# schemat.net
KiCad netlist of a schematic drawn in EAGLE
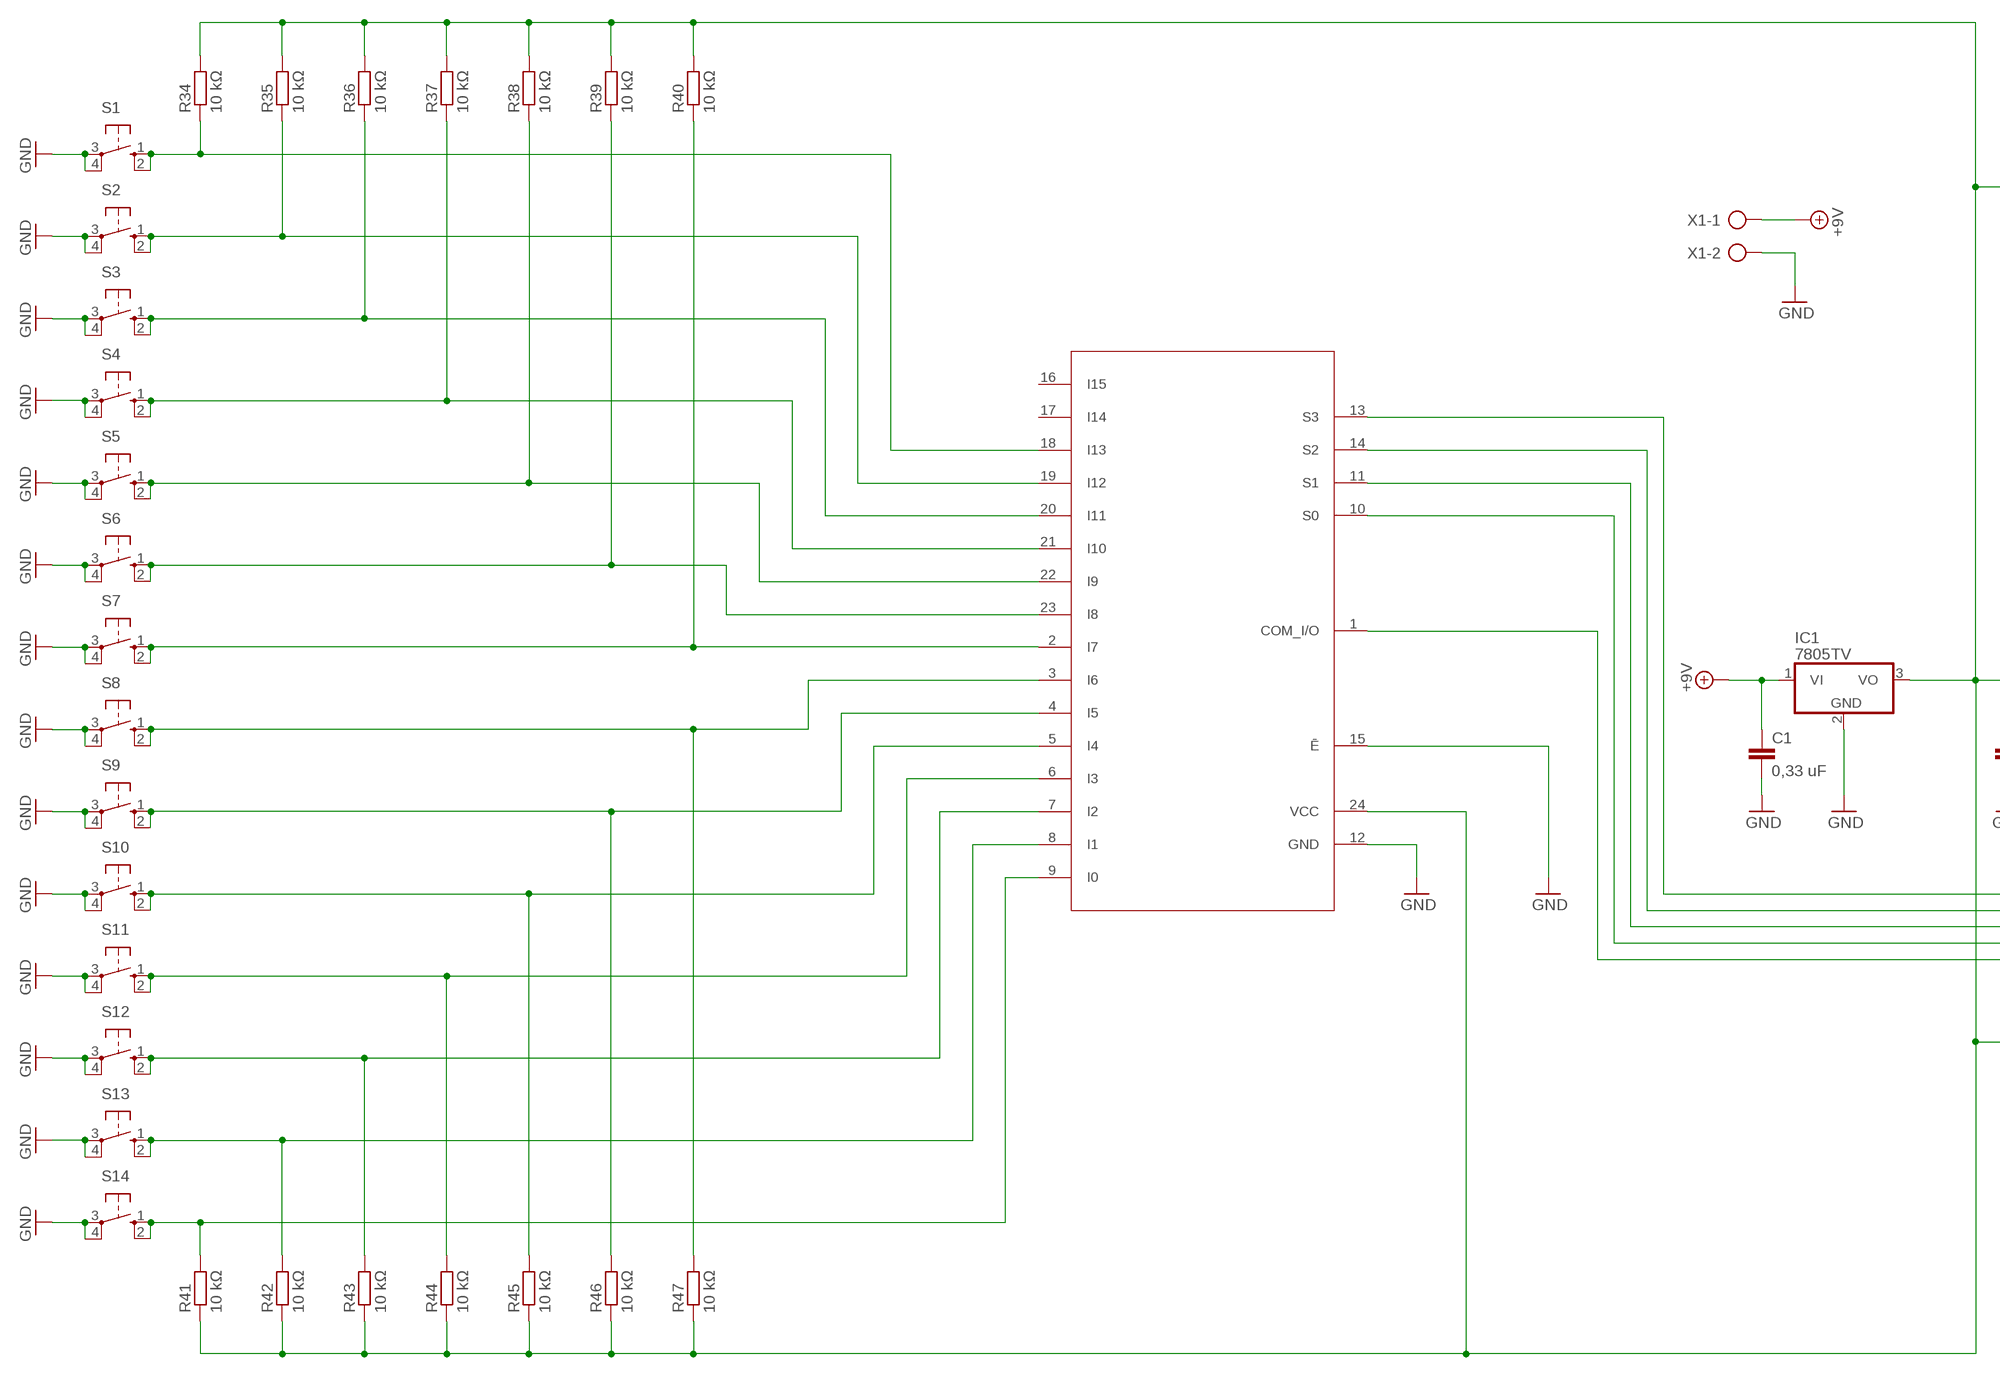
[diagram p0: schematic, sheet 1, part 1 of 2]
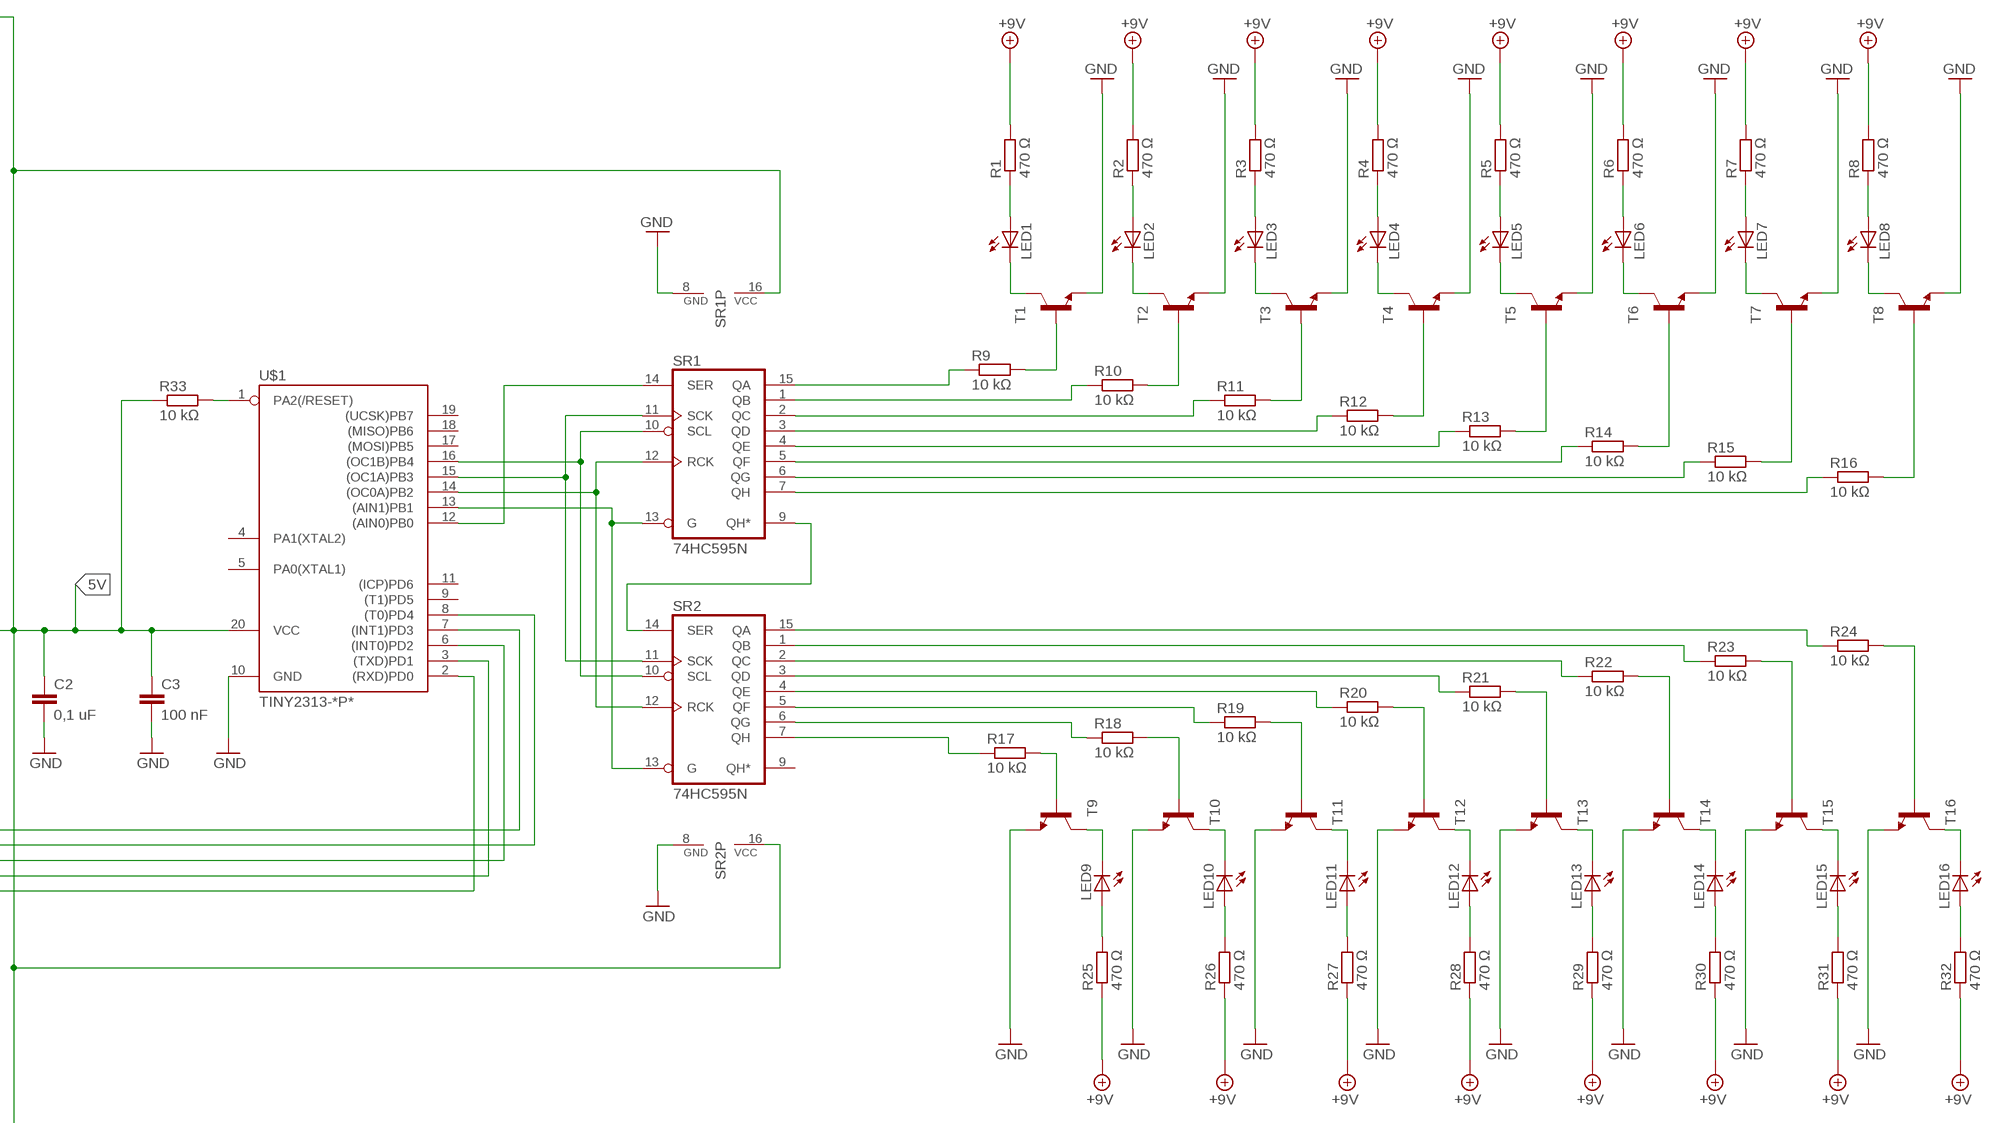
[diagram p1: schematic, sheet 1, part 2 of 2]

(export (version "E")
  (design (tool "Eeschema 10.0.6"))
  (components
    (comp (ref "C1")
      (value "0,33 uF")
      (footprint "eagle-import:C025-024X044")
      (libsource (lib "eagle-import") (part "C-EU025-024X044"))
    )
    (comp (ref "C2")
      (value "0,1 uF")
      (footprint "eagle-import:C025-024X044")
      (libsource (lib "eagle-import") (part "C-EU025-024X044"))
    )
    (comp (ref "C3")
      (value "100 nF")
      (footprint "eagle-import:C025-024X044")
      (libsource (lib "eagle-import") (part "C-EU025-024X044"))
    )
    (comp (ref "IC1")
      (value "7805TV")
      (footprint "eagle-import:TO220V")
      (libsource (lib "eagle-import") (part "78TV05"))
    )
    (comp (ref "LED1")
      (value "LED5MM")
      (footprint "eagle-import:LED5MM")
      (libsource (lib "eagle-import") (part "LED5MM"))
    )
    (comp (ref "LED2")
      (value "LED5MM")
      (footprint "eagle-import:LED5MM")
      (libsource (lib "eagle-import") (part "LED5MM"))
    )
    (comp (ref "LED3")
      (value "LED5MM")
      (footprint "eagle-import:LED5MM")
      (libsource (lib "eagle-import") (part "LED5MM"))
    )
    (comp (ref "LED4")
      (value "LED5MM")
      (footprint "eagle-import:LED5MM")
      (libsource (lib "eagle-import") (part "LED5MM"))
    )
    (comp (ref "LED5")
      (value "LED5MM")
      (footprint "eagle-import:LED5MM")
      (libsource (lib "eagle-import") (part "LED5MM"))
    )
    (comp (ref "LED6")
      (value "LED5MM")
      (footprint "eagle-import:LED5MM")
      (libsource (lib "eagle-import") (part "LED5MM"))
    )
    (comp (ref "LED7")
      (value "LED5MM")
      (footprint "eagle-import:LED5MM")
      (libsource (lib "eagle-import") (part "LED5MM"))
    )
    (comp (ref "LED8")
      (value "LED5MM")
      (footprint "eagle-import:LED5MM")
      (libsource (lib "eagle-import") (part "LED5MM"))
    )
    (comp (ref "LED9")
      (value "LED5MM")
      (footprint "eagle-import:LED5MM")
      (libsource (lib "eagle-import") (part "LED5MM"))
    )
    (comp (ref "LED10")
      (value "LED5MM")
      (footprint "eagle-import:LED5MM")
      (libsource (lib "eagle-import") (part "LED5MM"))
    )
    (comp (ref "LED11")
      (value "LED5MM")
      (footprint "eagle-import:LED5MM")
      (libsource (lib "eagle-import") (part "LED5MM"))
    )
    (comp (ref "LED12")
      (value "LED5MM")
      (footprint "eagle-import:LED5MM")
      (libsource (lib "eagle-import") (part "LED5MM"))
    )
    (comp (ref "LED13")
      (value "LED5MM")
      (footprint "eagle-import:LED5MM")
      (libsource (lib "eagle-import") (part "LED5MM"))
    )
    (comp (ref "LED14")
      (value "LED5MM")
      (footprint "eagle-import:LED5MM")
      (libsource (lib "eagle-import") (part "LED5MM"))
    )
    (comp (ref "LED15")
      (value "LED5MM")
      (footprint "eagle-import:LED5MM")
      (libsource (lib "eagle-import") (part "LED5MM"))
    )
    (comp (ref "LED16")
      (value "LED5MM")
      (footprint "eagle-import:LED5MM")
      (libsource (lib "eagle-import") (part "LED5MM"))
    )
    (comp (ref "R1")
      (value "470 Ω")
      (footprint "eagle-import:0207_10")
      (libsource (lib "eagle-import") (part "R-EU_0207/10"))
    )
    (comp (ref "R2")
      (value "470 Ω")
      (footprint "eagle-import:0207_10")
      (libsource (lib "eagle-import") (part "R-EU_0207/10"))
    )
    (comp (ref "R3")
      (value "470 Ω")
      (footprint "eagle-import:0207_10")
      (libsource (lib "eagle-import") (part "R-EU_0207/10"))
    )
    (comp (ref "R4")
      (value "470 Ω")
      (footprint "eagle-import:0207_10")
      (libsource (lib "eagle-import") (part "R-EU_0207/10"))
    )
    (comp (ref "R5")
      (value "470 Ω")
      (footprint "eagle-import:0207_10")
      (libsource (lib "eagle-import") (part "R-EU_0207/10"))
    )
    (comp (ref "R6")
      (value "470 Ω")
      (footprint "eagle-import:0207_10")
      (libsource (lib "eagle-import") (part "R-EU_0207/10"))
    )
    (comp (ref "R7")
      (value "470 Ω")
      (footprint "eagle-import:0207_10")
      (libsource (lib "eagle-import") (part "R-EU_0207/10"))
    )
    (comp (ref "R8")
      (value "470 Ω")
      (footprint "eagle-import:0207_10")
      (libsource (lib "eagle-import") (part "R-EU_0207/10"))
    )
    (comp (ref "R9")
      (value "10 kΩ")
      (footprint "eagle-import:0207_10")
      (libsource (lib "eagle-import") (part "R-EU_0207/10"))
    )
    (comp (ref "R10")
      (value "10 kΩ")
      (footprint "eagle-import:0207_10")
      (libsource (lib "eagle-import") (part "R-EU_0207/10"))
    )
    (comp (ref "R11")
      (value "10 kΩ")
      (footprint "eagle-import:0207_10")
      (libsource (lib "eagle-import") (part "R-EU_0207/10"))
    )
    (comp (ref "R12")
      (value "10 kΩ")
      (footprint "eagle-import:0207_10")
      (libsource (lib "eagle-import") (part "R-EU_0207/10"))
    )
    (comp (ref "R13")
      (value "10 kΩ")
      (footprint "eagle-import:0207_10")
      (libsource (lib "eagle-import") (part "R-EU_0207/10"))
    )
    (comp (ref "R14")
      (value "10 kΩ")
      (footprint "eagle-import:0207_10")
      (libsource (lib "eagle-import") (part "R-EU_0207/10"))
    )
    (comp (ref "R15")
      (value "10 kΩ")
      (footprint "eagle-import:0207_10")
      (libsource (lib "eagle-import") (part "R-EU_0207/10"))
    )
    (comp (ref "R16")
      (value "10 kΩ")
      (footprint "eagle-import:0207_10")
      (libsource (lib "eagle-import") (part "R-EU_0207/10"))
    )
    (comp (ref "R17")
      (value "10 kΩ")
      (footprint "eagle-import:0207_10")
      (libsource (lib "eagle-import") (part "R-EU_0207/10"))
    )
    (comp (ref "R18")
      (value "10 kΩ")
      (footprint "eagle-import:0207_10")
      (libsource (lib "eagle-import") (part "R-EU_0207/10"))
    )
    (comp (ref "R19")
      (value "10 kΩ")
      (footprint "eagle-import:0207_10")
      (libsource (lib "eagle-import") (part "R-EU_0207/10"))
    )
    (comp (ref "R20")
      (value "10 kΩ")
      (footprint "eagle-import:0207_10")
      (libsource (lib "eagle-import") (part "R-EU_0207/10"))
    )
    (comp (ref "R21")
      (value "10 kΩ")
      (footprint "eagle-import:0207_10")
      (libsource (lib "eagle-import") (part "R-EU_0207/10"))
    )
    (comp (ref "R22")
      (value "10 kΩ")
      (footprint "eagle-import:0207_10")
      (libsource (lib "eagle-import") (part "R-EU_0207/10"))
    )
    (comp (ref "R23")
      (value "10 kΩ")
      (footprint "eagle-import:0207_10")
      (libsource (lib "eagle-import") (part "R-EU_0207/10"))
    )
    (comp (ref "R24")
      (value "10 kΩ")
      (footprint "eagle-import:0207_10")
      (libsource (lib "eagle-import") (part "R-EU_0207/10"))
    )
    (comp (ref "R25")
      (value "470 Ω")
      (footprint "eagle-import:0207_10")
      (libsource (lib "eagle-import") (part "R-EU_0207/10"))
    )
    (comp (ref "R26")
      (value "470 Ω")
      (footprint "eagle-import:0207_10")
      (libsource (lib "eagle-import") (part "R-EU_0207/10"))
    )
    (comp (ref "R27")
      (value "470 Ω")
      (footprint "eagle-import:0207_10")
      (libsource (lib "eagle-import") (part "R-EU_0207/10"))
    )
    (comp (ref "R28")
      (value "470 Ω")
      (footprint "eagle-import:0207_10")
      (libsource (lib "eagle-import") (part "R-EU_0207/10"))
    )
    (comp (ref "R29")
      (value "470 Ω")
      (footprint "eagle-import:0207_10")
      (libsource (lib "eagle-import") (part "R-EU_0207/10"))
    )
    (comp (ref "R30")
      (value "470 Ω")
      (footprint "eagle-import:0207_10")
      (libsource (lib "eagle-import") (part "R-EU_0207/10"))
    )
    (comp (ref "R31")
      (value "470 Ω")
      (footprint "eagle-import:0207_10")
      (libsource (lib "eagle-import") (part "R-EU_0207/10"))
    )
    (comp (ref "R32")
      (value "470 Ω")
      (footprint "eagle-import:0207_10")
      (libsource (lib "eagle-import") (part "R-EU_0207/10"))
    )
    (comp (ref "R33")
      (value "10 kΩ")
      (footprint "eagle-import:0207_10")
      (libsource (lib "eagle-import") (part "R-EU_0207/10"))
    )
    (comp (ref "R34")
      (value "10 kΩ")
      (footprint "eagle-import:0207_10")
      (libsource (lib "eagle-import") (part "R-EU_0207/10"))
    )
    (comp (ref "R35")
      (value "10 kΩ")
      (footprint "eagle-import:0207_10")
      (libsource (lib "eagle-import") (part "R-EU_0207/10"))
    )
    (comp (ref "R36")
      (value "10 kΩ")
      (footprint "eagle-import:0207_10")
      (libsource (lib "eagle-import") (part "R-EU_0207/10"))
    )
    (comp (ref "R37")
      (value "10 kΩ")
      (footprint "eagle-import:0207_10")
      (libsource (lib "eagle-import") (part "R-EU_0207/10"))
    )
    (comp (ref "R38")
      (value "10 kΩ")
      (footprint "eagle-import:0207_10")
      (libsource (lib "eagle-import") (part "R-EU_0207/10"))
    )
    (comp (ref "R39")
      (value "10 kΩ")
      (footprint "eagle-import:0207_10")
      (libsource (lib "eagle-import") (part "R-EU_0207/10"))
    )
    (comp (ref "R40")
      (value "10 kΩ")
      (footprint "eagle-import:0207_10")
      (libsource (lib "eagle-import") (part "R-EU_0207/10"))
    )
    (comp (ref "R41")
      (value "10 kΩ")
      (footprint "eagle-import:0207_10")
      (libsource (lib "eagle-import") (part "R-EU_0207/10"))
    )
    (comp (ref "R42")
      (value "10 kΩ")
      (footprint "eagle-import:0207_10")
      (libsource (lib "eagle-import") (part "R-EU_0207/10"))
    )
    (comp (ref "R43")
      (value "10 kΩ")
      (footprint "eagle-import:0207_10")
      (libsource (lib "eagle-import") (part "R-EU_0207/10"))
    )
    (comp (ref "R44")
      (value "10 kΩ")
      (footprint "eagle-import:0207_10")
      (libsource (lib "eagle-import") (part "R-EU_0207/10"))
    )
    (comp (ref "R45")
      (value "10 kΩ")
      (footprint "eagle-import:0207_10")
      (libsource (lib "eagle-import") (part "R-EU_0207/10"))
    )
    (comp (ref "R46")
      (value "10 kΩ")
      (footprint "eagle-import:0207_10")
      (libsource (lib "eagle-import") (part "R-EU_0207/10"))
    )
    (comp (ref "R47")
      (value "10 kΩ")
      (footprint "eagle-import:0207_10")
      (libsource (lib "eagle-import") (part "R-EU_0207/10"))
    )
    (comp (ref "S1")
      (value "40-XX")
      (footprint "eagle-import:B3F-40XX")
      (fields (field (name "MF") "OMRON COMPONENTS USA") (field (name "MPN") "B3F-4000"))
      (libsource (lib "eagle-import") (part "40-XX"))
    )
    (comp (ref "S2")
      (value "40-XX")
      (footprint "eagle-import:B3F-40XX")
      (fields (field (name "MF") "OMRON COMPONENTS USA") (field (name "MPN") "B3F-4000"))
      (libsource (lib "eagle-import") (part "40-XX"))
    )
    (comp (ref "S3")
      (value "40-XX")
      (footprint "eagle-import:B3F-40XX")
      (fields (field (name "MF") "OMRON COMPONENTS USA") (field (name "MPN") "B3F-4000"))
      (libsource (lib "eagle-import") (part "40-XX"))
    )
    (comp (ref "S4")
      (value "40-XX")
      (footprint "eagle-import:B3F-40XX")
      (fields (field (name "MF") "OMRON COMPONENTS USA") (field (name "MPN") "B3F-4000"))
      (libsource (lib "eagle-import") (part "40-XX"))
    )
    (comp (ref "S5")
      (value "40-XX")
      (footprint "eagle-import:B3F-40XX")
      (fields (field (name "MF") "OMRON COMPONENTS USA") (field (name "MPN") "B3F-4000"))
      (libsource (lib "eagle-import") (part "40-XX"))
    )
    (comp (ref "S6")
      (value "40-XX")
      (footprint "eagle-import:B3F-40XX")
      (fields (field (name "MF") "OMRON COMPONENTS USA") (field (name "MPN") "B3F-4000"))
      (libsource (lib "eagle-import") (part "40-XX"))
    )
    (comp (ref "S7")
      (value "40-XX")
      (footprint "eagle-import:B3F-40XX")
      (fields (field (name "MF") "OMRON COMPONENTS USA") (field (name "MPN") "B3F-4000"))
      (libsource (lib "eagle-import") (part "40-XX"))
    )
    (comp (ref "S8")
      (value "40-XX")
      (footprint "eagle-import:B3F-40XX")
      (fields (field (name "MF") "OMRON COMPONENTS USA") (field (name "MPN") "B3F-4000"))
      (libsource (lib "eagle-import") (part "40-XX"))
    )
    (comp (ref "S9")
      (value "40-XX")
      (footprint "eagle-import:B3F-40XX")
      (fields (field (name "MF") "OMRON COMPONENTS USA") (field (name "MPN") "B3F-4000"))
      (libsource (lib "eagle-import") (part "40-XX"))
    )
    (comp (ref "S10")
      (value "40-XX")
      (footprint "eagle-import:B3F-40XX")
      (fields (field (name "MF") "OMRON COMPONENTS USA") (field (name "MPN") "B3F-4000"))
      (libsource (lib "eagle-import") (part "40-XX"))
    )
    (comp (ref "S11")
      (value "40-XX")
      (footprint "eagle-import:B3F-40XX")
      (fields (field (name "MF") "OMRON COMPONENTS USA") (field (name "MPN") "B3F-4000"))
      (libsource (lib "eagle-import") (part "40-XX"))
    )
    (comp (ref "S12")
      (value "40-XX")
      (footprint "eagle-import:B3F-40XX")
      (fields (field (name "MF") "OMRON COMPONENTS USA") (field (name "MPN") "B3F-4000"))
      (libsource (lib "eagle-import") (part "40-XX"))
    )
    (comp (ref "S13")
      (value "40-XX")
      (footprint "eagle-import:B3F-40XX")
      (fields (field (name "MF") "OMRON COMPONENTS USA") (field (name "MPN") "B3F-4000"))
      (libsource (lib "eagle-import") (part "40-XX"))
    )
    (comp (ref "S14")
      (value "40-XX")
      (footprint "eagle-import:B3F-40XX")
      (fields (field (name "MF") "OMRON COMPONENTS USA") (field (name "MPN") "B3F-4000"))
      (libsource (lib "eagle-import") (part "40-XX"))
    )
    (comp (ref "SR1")
      (value "74HC595N")
      (footprint "eagle-import:DIL16")
      (fields (field (name "SPICEPREFIX") "I"))
      (libsource (lib "eagle-import") (part "74595NHC"))
    )
    (comp (ref "SR2")
      (value "74HC595N")
      (footprint "eagle-import:DIL16")
      (libsource (lib "eagle-import") (part "74595NHC"))
    )
    (comp (ref "T1")
      (value "-NPN-TO92")
      (footprint "eagle-import:TO92")
      (libsource (lib "eagle-import") (part "-NPN-TO92"))
    )
    (comp (ref "T2")
      (value "-NPN-TO92")
      (footprint "eagle-import:TO92")
      (libsource (lib "eagle-import") (part "-NPN-TO92"))
    )
    (comp (ref "T3")
      (value "-NPN-TO92")
      (footprint "eagle-import:TO92")
      (libsource (lib "eagle-import") (part "-NPN-TO92"))
    )
    (comp (ref "T4")
      (value "-NPN-TO92")
      (footprint "eagle-import:TO92")
      (libsource (lib "eagle-import") (part "-NPN-TO92"))
    )
    (comp (ref "T5")
      (value "-NPN-TO92")
      (footprint "eagle-import:TO92")
      (libsource (lib "eagle-import") (part "-NPN-TO92"))
    )
    (comp (ref "T6")
      (value "-NPN-TO92")
      (footprint "eagle-import:TO92")
      (libsource (lib "eagle-import") (part "-NPN-TO92"))
    )
    (comp (ref "T7")
      (value "-NPN-TO92")
      (footprint "eagle-import:TO92")
      (libsource (lib "eagle-import") (part "-NPN-TO92"))
    )
    (comp (ref "T8")
      (value "-NPN-TO92")
      (footprint "eagle-import:TO92")
      (libsource (lib "eagle-import") (part "-NPN-TO92"))
    )
    (comp (ref "T9")
      (value "-NPN-TO92")
      (footprint "eagle-import:TO92")
      (libsource (lib "eagle-import") (part "-NPN-TO92"))
    )
    (comp (ref "T10")
      (value "-NPN-TO92")
      (footprint "eagle-import:TO92")
      (libsource (lib "eagle-import") (part "-NPN-TO92"))
    )
    (comp (ref "T11")
      (value "-NPN-TO92")
      (footprint "eagle-import:TO92")
      (libsource (lib "eagle-import") (part "-NPN-TO92"))
    )
    (comp (ref "T12")
      (value "-NPN-TO92")
      (footprint "eagle-import:TO92")
      (libsource (lib "eagle-import") (part "-NPN-TO92"))
    )
    (comp (ref "T13")
      (value "-NPN-TO92")
      (footprint "eagle-import:TO92")
      (libsource (lib "eagle-import") (part "-NPN-TO92"))
    )
    (comp (ref "T14")
      (value "-NPN-TO92")
      (footprint "eagle-import:TO92")
      (libsource (lib "eagle-import") (part "-NPN-TO92"))
    )
    (comp (ref "T15")
      (value "-NPN-TO92")
      (footprint "eagle-import:TO92")
      (libsource (lib "eagle-import") (part "-NPN-TO92"))
    )
    (comp (ref "T16")
      (value "-NPN-TO92")
      (footprint "eagle-import:TO92")
      (libsource (lib "eagle-import") (part "-NPN-TO92"))
    )
    (comp (ref "U$1")
      (value "TINY2313-*P*")
      (footprint "eagle-import:DIL20")
      (libsource (lib "eagle-import") (part "TINY2313-P"))
    )
    (comp (ref "U$2")
      (value "CD74HC4067")
      (footprint "eagle-import:DIL24-6")
      (libsource (lib "eagle-import") (part "CD74HC4067"))
    )
    (comp (ref "X1")
      (value "AK500/2")
      (footprint "eagle-import:AK500_2")
      (libsource (lib "eagle-import") (part "AK500/2"))
    )
  )
  (nets
    (net (code "1") (name "+9V") (class "Default")
      (node (ref "C1") (pin "1") (pinfunction "1_1") (pintype "passive"))
      (node (ref "IC1") (pin "1") (pinfunction "VI_1") (pintype "input"))
      (node (ref "R1") (pin "2") (pinfunction "2_2") (pintype "passive"))
      (node (ref "R2") (pin "2") (pinfunction "2_2") (pintype "passive"))
      (node (ref "R25") (pin "1") (pinfunction "1_1") (pintype "passive"))
      (node (ref "R26") (pin "1") (pinfunction "1_1") (pintype "passive"))
      (node (ref "R27") (pin "1") (pinfunction "1_1") (pintype "passive"))
      (node (ref "R28") (pin "1") (pinfunction "1_1") (pintype "passive"))
      (node (ref "R29") (pin "1") (pinfunction "1_1") (pintype "passive"))
      (node (ref "R3") (pin "2") (pinfunction "2_2") (pintype "passive"))
      (node (ref "R30") (pin "1") (pinfunction "1_1") (pintype "passive"))
      (node (ref "R31") (pin "1") (pinfunction "1_1") (pintype "passive"))
      (node (ref "R32") (pin "1") (pinfunction "1_1") (pintype "passive"))
      (node (ref "R4") (pin "2") (pinfunction "2_2") (pintype "passive"))
      (node (ref "R5") (pin "2") (pinfunction "2_2") (pintype "passive"))
      (node (ref "R6") (pin "2") (pinfunction "2_2") (pintype "passive"))
      (node (ref "R7") (pin "2") (pinfunction "2_2") (pintype "passive"))
      (node (ref "R8") (pin "2") (pinfunction "2_2") (pintype "passive"))
      (node (ref "X1") (pin "1") (pinfunction "KL_1") (pintype "passive"))
    )
    (net (code "2") (name "5V") (class "Default")
      (node (ref "C2") (pin "1") (pinfunction "1_1") (pintype "passive"))
      (node (ref "C3") (pin "1") (pinfunction "1_1") (pintype "passive"))
      (node (ref "IC1") (pin "3") (pinfunction "VO_3") (pintype "passive"))
      (node (ref "R33") (pin "1") (pinfunction "1_1") (pintype "passive"))
      (node (ref "R34") (pin "2") (pinfunction "2_2") (pintype "passive"))
      (node (ref "R35") (pin "2") (pinfunction "2_2") (pintype "passive"))
      (node (ref "R36") (pin "2") (pinfunction "2_2") (pintype "passive"))
      (node (ref "R37") (pin "2") (pinfunction "2_2") (pintype "passive"))
      (node (ref "R38") (pin "2") (pinfunction "2_2") (pintype "passive"))
      (node (ref "R39") (pin "2") (pinfunction "2_2") (pintype "passive"))
      (node (ref "R40") (pin "2") (pinfunction "2_2") (pintype "passive"))
      (node (ref "R41") (pin "1") (pinfunction "1_1") (pintype "passive"))
      (node (ref "R42") (pin "1") (pinfunction "1_1") (pintype "passive"))
      (node (ref "R43") (pin "1") (pinfunction "1_1") (pintype "passive"))
      (node (ref "R44") (pin "1") (pinfunction "1_1") (pintype "passive"))
      (node (ref "R45") (pin "1") (pinfunction "1_1") (pintype "passive"))
      (node (ref "R46") (pin "1") (pinfunction "1_1") (pintype "passive"))
      (node (ref "R47") (pin "1") (pinfunction "1_1") (pintype "passive"))
      (node (ref "SR1") (pin "16") (pinfunction "VCC_16") (pintype "power_in"))
      (node (ref "SR2") (pin "16") (pinfunction "VCC_16") (pintype "power_in"))
      (node (ref "U$1") (pin "20") (pinfunction "VCC_20") (pintype "power_in"))
      (node (ref "U$2") (pin "24") (pinfunction "VCC_24") (pintype "bidirectional"))
    )
    (net (code "3") (name "GND") (class "Default")
      (node (ref "C1") (pin "2") (pinfunction "2_2") (pintype "passive"))
      (node (ref "C2") (pin "2") (pinfunction "2_2") (pintype "passive"))
      (node (ref "C3") (pin "2") (pinfunction "2_2") (pintype "passive"))
      (node (ref "IC1") (pin "2") (pinfunction "GND_2") (pintype "passive"))
      (node (ref "S1") (pin "3") (pinfunction "P_3") (pintype "passive"))
      (node (ref "S1") (pin "4") (pinfunction "P1_4") (pintype "passive"))
      (node (ref "S10") (pin "3") (pinfunction "P_3") (pintype "passive"))
      (node (ref "S10") (pin "4") (pinfunction "P1_4") (pintype "passive"))
      (node (ref "S11") (pin "3") (pinfunction "P_3") (pintype "passive"))
      (node (ref "S11") (pin "4") (pinfunction "P1_4") (pintype "passive"))
      (node (ref "S12") (pin "3") (pinfunction "P_3") (pintype "passive"))
      (node (ref "S12") (pin "4") (pinfunction "P1_4") (pintype "passive"))
      (node (ref "S13") (pin "3") (pinfunction "P_3") (pintype "passive"))
      (node (ref "S13") (pin "4") (pinfunction "P1_4") (pintype "passive"))
      (node (ref "S14") (pin "3") (pinfunction "P_3") (pintype "passive"))
      (node (ref "S14") (pin "4") (pinfunction "P1_4") (pintype "passive"))
      (node (ref "S2") (pin "3") (pinfunction "P_3") (pintype "passive"))
      (node (ref "S2") (pin "4") (pinfunction "P1_4") (pintype "passive"))
      (node (ref "S3") (pin "3") (pinfunction "P_3") (pintype "passive"))
      (node (ref "S3") (pin "4") (pinfunction "P1_4") (pintype "passive"))
      (node (ref "S4") (pin "3") (pinfunction "P_3") (pintype "passive"))
      (node (ref "S4") (pin "4") (pinfunction "P1_4") (pintype "passive"))
      (node (ref "S5") (pin "3") (pinfunction "P_3") (pintype "passive"))
      (node (ref "S5") (pin "4") (pinfunction "P1_4") (pintype "passive"))
      (node (ref "S6") (pin "3") (pinfunction "P_3") (pintype "passive"))
      (node (ref "S6") (pin "4") (pinfunction "P1_4") (pintype "passive"))
      (node (ref "S7") (pin "3") (pinfunction "P_3") (pintype "passive"))
      (node (ref "S7") (pin "4") (pinfunction "P1_4") (pintype "passive"))
      (node (ref "S8") (pin "3") (pinfunction "P_3") (pintype "passive"))
      (node (ref "S8") (pin "4") (pinfunction "P1_4") (pintype "passive"))
      (node (ref "S9") (pin "3") (pinfunction "P_3") (pintype "passive"))
      (node (ref "S9") (pin "4") (pinfunction "P1_4") (pintype "passive"))
      (node (ref "SR1") (pin "8") (pinfunction "GND_8") (pintype "power_in"))
      (node (ref "SR2") (pin "8") (pinfunction "GND_8") (pintype "power_in"))
      (node (ref "T1") (pin "1") (pinfunction "E_1") (pintype "passive"))
      (node (ref "T10") (pin "1") (pinfunction "E_1") (pintype "passive"))
      (node (ref "T11") (pin "1") (pinfunction "E_1") (pintype "passive"))
      (node (ref "T12") (pin "1") (pinfunction "E_1") (pintype "passive"))
      (node (ref "T13") (pin "1") (pinfunction "E_1") (pintype "passive"))
      (node (ref "T14") (pin "1") (pinfunction "E_1") (pintype "passive"))
      (node (ref "T15") (pin "1") (pinfunction "E_1") (pintype "passive"))
      (node (ref "T16") (pin "1") (pinfunction "E_1") (pintype "passive"))
      (node (ref "T2") (pin "1") (pinfunction "E_1") (pintype "passive"))
      (node (ref "T3") (pin "1") (pinfunction "E_1") (pintype "passive"))
      (node (ref "T4") (pin "1") (pinfunction "E_1") (pintype "passive"))
      (node (ref "T5") (pin "1") (pinfunction "E_1") (pintype "passive"))
      (node (ref "T6") (pin "1") (pinfunction "E_1") (pintype "passive"))
      (node (ref "T7") (pin "1") (pinfunction "E_1") (pintype "passive"))
      (node (ref "T8") (pin "1") (pinfunction "E_1") (pintype "passive"))
      (node (ref "T9") (pin "1") (pinfunction "E_1") (pintype "passive"))
      (node (ref "U$1") (pin "10") (pinfunction "GND_10") (pintype "power_in"))
      (node (ref "U$2") (pin "12") (pinfunction "GND_12") (pintype "bidirectional"))
      (node (ref "U$2") (pin "15") (pinfunction "Ē_15") (pintype "bidirectional"))
      (node (ref "X1") (pin "2") (pinfunction "KL_2") (pintype "passive"))
    )
    (net (code "4") (name "Net-(LED1-C)") (class "Default")
      (node (ref "LED1") (pin "K") (pinfunction "C_K") (pintype "passive"))
      (node (ref "T1") (pin "3") (pinfunction "C_3") (pintype "passive"))
    )
    (net (code "5") (name "Net-(LED1-PadA)") (class "Default")
      (node (ref "LED1") (pin "A") (pinfunction "A_A") (pintype "passive"))
      (node (ref "R1") (pin "1") (pinfunction "1_1") (pintype "passive"))
    )
    (net (code "6") (name "Net-(LED2-C)") (class "Default")
      (node (ref "LED2") (pin "K") (pinfunction "C_K") (pintype "passive"))
      (node (ref "T2") (pin "3") (pinfunction "C_3") (pintype "passive"))
    )
    (net (code "7") (name "Net-(LED2-PadA)") (class "Default")
      (node (ref "LED2") (pin "A") (pinfunction "A_A") (pintype "passive"))
      (node (ref "R2") (pin "1") (pinfunction "1_1") (pintype "passive"))
    )
    (net (code "8") (name "Net-(LED3-C)") (class "Default")
      (node (ref "LED3") (pin "K") (pinfunction "C_K") (pintype "passive"))
      (node (ref "T3") (pin "3") (pinfunction "C_3") (pintype "passive"))
    )
    (net (code "9") (name "Net-(LED3-PadA)") (class "Default")
      (node (ref "LED3") (pin "A") (pinfunction "A_A") (pintype "passive"))
      (node (ref "R3") (pin "1") (pinfunction "1_1") (pintype "passive"))
    )
    (net (code "10") (name "Net-(LED4-C)") (class "Default")
      (node (ref "LED4") (pin "K") (pinfunction "C_K") (pintype "passive"))
      (node (ref "T4") (pin "3") (pinfunction "C_3") (pintype "passive"))
    )
    (net (code "11") (name "Net-(LED4-PadA)") (class "Default")
      (node (ref "LED4") (pin "A") (pinfunction "A_A") (pintype "passive"))
      (node (ref "R4") (pin "1") (pinfunction "1_1") (pintype "passive"))
    )
    (net (code "12") (name "Net-(LED5-C)") (class "Default")
      (node (ref "LED5") (pin "K") (pinfunction "C_K") (pintype "passive"))
      (node (ref "T5") (pin "3") (pinfunction "C_3") (pintype "passive"))
    )
    (net (code "13") (name "Net-(LED5-PadA)") (class "Default")
      (node (ref "LED5") (pin "A") (pinfunction "A_A") (pintype "passive"))
      (node (ref "R5") (pin "1") (pinfunction "1_1") (pintype "passive"))
    )
    (net (code "14") (name "Net-(LED6-C)") (class "Default")
      (node (ref "LED6") (pin "K") (pinfunction "C_K") (pintype "passive"))
      (node (ref "T6") (pin "3") (pinfunction "C_3") (pintype "passive"))
    )
    (net (code "15") (name "Net-(LED6-PadA)") (class "Default")
      (node (ref "LED6") (pin "A") (pinfunction "A_A") (pintype "passive"))
      (node (ref "R6") (pin "1") (pinfunction "1_1") (pintype "passive"))
    )
    (net (code "16") (name "Net-(LED7-C)") (class "Default")
      (node (ref "LED7") (pin "K") (pinfunction "C_K") (pintype "passive"))
      (node (ref "T7") (pin "3") (pinfunction "C_3") (pintype "passive"))
    )
    (net (code "17") (name "Net-(LED7-PadA)") (class "Default")
      (node (ref "LED7") (pin "A") (pinfunction "A_A") (pintype "passive"))
      (node (ref "R7") (pin "1") (pinfunction "1_1") (pintype "passive"))
    )
    (net (code "18") (name "Net-(LED8-C)") (class "Default")
      (node (ref "LED8") (pin "K") (pinfunction "C_K") (pintype "passive"))
      (node (ref "T8") (pin "3") (pinfunction "C_3") (pintype "passive"))
    )
    (net (code "19") (name "Net-(LED8-PadA)") (class "Default")
      (node (ref "LED8") (pin "A") (pinfunction "A_A") (pintype "passive"))
      (node (ref "R8") (pin "1") (pinfunction "1_1") (pintype "passive"))
    )
    (net (code "20") (name "Net-(LED9-C)") (class "Default")
      (node (ref "LED9") (pin "K") (pinfunction "C_K") (pintype "passive"))
      (node (ref "T9") (pin "3") (pinfunction "C_3") (pintype "passive"))
    )
    (net (code "21") (name "Net-(LED9-PadA)") (class "Default")
      (node (ref "LED9") (pin "A") (pinfunction "A_A") (pintype "passive"))
      (node (ref "R25") (pin "2") (pinfunction "2_2") (pintype "passive"))
    )
    (net (code "22") (name "Net-(LED10-C)") (class "Default")
      (node (ref "LED10") (pin "K") (pinfunction "C_K") (pintype "passive"))
      (node (ref "T10") (pin "3") (pinfunction "C_3") (pintype "passive"))
    )
    (net (code "23") (name "Net-(LED10-PadA)") (class "Default")
      (node (ref "LED10") (pin "A") (pinfunction "A_A") (pintype "passive"))
      (node (ref "R26") (pin "2") (pinfunction "2_2") (pintype "passive"))
    )
    (net (code "24") (name "Net-(LED11-C)") (class "Default")
      (node (ref "LED11") (pin "K") (pinfunction "C_K") (pintype "passive"))
      (node (ref "T11") (pin "3") (pinfunction "C_3") (pintype "passive"))
    )
    (net (code "25") (name "Net-(LED11-PadA)") (class "Default")
      (node (ref "LED11") (pin "A") (pinfunction "A_A") (pintype "passive"))
      (node (ref "R27") (pin "2") (pinfunction "2_2") (pintype "passive"))
    )
    (net (code "26") (name "Net-(LED12-C)") (class "Default")
      (node (ref "LED12") (pin "K") (pinfunction "C_K") (pintype "passive"))
      (node (ref "T12") (pin "3") (pinfunction "C_3") (pintype "passive"))
    )
    (net (code "27") (name "Net-(LED12-PadA)") (class "Default")
      (node (ref "LED12") (pin "A") (pinfunction "A_A") (pintype "passive"))
      (node (ref "R28") (pin "2") (pinfunction "2_2") (pintype "passive"))
    )
    (net (code "28") (name "Net-(LED13-C)") (class "Default")
      (node (ref "LED13") (pin "K") (pinfunction "C_K") (pintype "passive"))
      (node (ref "T13") (pin "3") (pinfunction "C_3") (pintype "passive"))
    )
    (net (code "29") (name "Net-(LED13-PadA)") (class "Default")
      (node (ref "LED13") (pin "A") (pinfunction "A_A") (pintype "passive"))
      (node (ref "R29") (pin "2") (pinfunction "2_2") (pintype "passive"))
    )
    (net (code "30") (name "Net-(LED14-C)") (class "Default")
      (node (ref "LED14") (pin "K") (pinfunction "C_K") (pintype "passive"))
      (node (ref "T14") (pin "3") (pinfunction "C_3") (pintype "passive"))
    )
    (net (code "31") (name "Net-(LED14-PadA)") (class "Default")
      (node (ref "LED14") (pin "A") (pinfunction "A_A") (pintype "passive"))
      (node (ref "R30") (pin "2") (pinfunction "2_2") (pintype "passive"))
    )
    (net (code "32") (name "Net-(LED15-C)") (class "Default")
      (node (ref "LED15") (pin "K") (pinfunction "C_K") (pintype "passive"))
      (node (ref "T15") (pin "3") (pinfunction "C_3") (pintype "passive"))
    )
    (net (code "33") (name "Net-(LED15-PadA)") (class "Default")
      (node (ref "LED15") (pin "A") (pinfunction "A_A") (pintype "passive"))
      (node (ref "R31") (pin "2") (pinfunction "2_2") (pintype "passive"))
    )
    (net (code "34") (name "Net-(LED16-C)") (class "Default")
      (node (ref "LED16") (pin "K") (pinfunction "C_K") (pintype "passive"))
      (node (ref "T16") (pin "3") (pinfunction "C_3") (pintype "passive"))
    )
    (net (code "35") (name "Net-(LED16-PadA)") (class "Default")
      (node (ref "LED16") (pin "A") (pinfunction "A_A") (pintype "passive"))
      (node (ref "R32") (pin "2") (pinfunction "2_2") (pintype "passive"))
    )
    (net (code "36") (name "Net-(S1-S)") (class "Default")
      (node (ref "R34") (pin "1") (pinfunction "1_1") (pintype "passive"))
      (node (ref "S1") (pin "1") (pinfunction "S_1") (pintype "passive"))
      (node (ref "S1") (pin "2") (pinfunction "S1_2") (pintype "passive"))
      (node (ref "U$2") (pin "18") (pinfunction "I13_18") (pintype "bidirectional"))
    )
    (net (code "37") (name "Net-(S2-S)") (class "Default")
      (node (ref "R35") (pin "1") (pinfunction "1_1") (pintype "passive"))
      (node (ref "S2") (pin "1") (pinfunction "S_1") (pintype "passive"))
      (node (ref "S2") (pin "2") (pinfunction "S1_2") (pintype "passive"))
      (node (ref "U$2") (pin "19") (pinfunction "I12_19") (pintype "bidirectional"))
    )
    (net (code "38") (name "Net-(S3-S)") (class "Default")
      (node (ref "R36") (pin "1") (pinfunction "1_1") (pintype "passive"))
      (node (ref "S3") (pin "1") (pinfunction "S_1") (pintype "passive"))
      (node (ref "S3") (pin "2") (pinfunction "S1_2") (pintype "passive"))
      (node (ref "U$2") (pin "20") (pinfunction "I11_20") (pintype "bidirectional"))
    )
    (net (code "39") (name "Net-(S4-S)") (class "Default")
      (node (ref "R37") (pin "1") (pinfunction "1_1") (pintype "passive"))
      (node (ref "S4") (pin "1") (pinfunction "S_1") (pintype "passive"))
      (node (ref "S4") (pin "2") (pinfunction "S1_2") (pintype "passive"))
      (node (ref "U$2") (pin "21") (pinfunction "I10_21") (pintype "bidirectional"))
    )
    (net (code "40") (name "Net-(S5-S)") (class "Default")
      (node (ref "R38") (pin "1") (pinfunction "1_1") (pintype "passive"))
      (node (ref "S5") (pin "1") (pinfunction "S_1") (pintype "passive"))
      (node (ref "S5") (pin "2") (pinfunction "S1_2") (pintype "passive"))
      (node (ref "U$2") (pin "22") (pinfunction "I9_22") (pintype "bidirectional"))
    )
    (net (code "41") (name "Net-(S6-S)") (class "Default")
      (node (ref "R39") (pin "1") (pinfunction "1_1") (pintype "passive"))
      (node (ref "S6") (pin "1") (pinfunction "S_1") (pintype "passive"))
      (node (ref "S6") (pin "2") (pinfunction "S1_2") (pintype "passive"))
      (node (ref "U$2") (pin "23") (pinfunction "I8_23") (pintype "bidirectional"))
    )
    (net (code "42") (name "Net-(S7-S)") (class "Default")
      (node (ref "R40") (pin "1") (pinfunction "1_1") (pintype "passive"))
      (node (ref "S7") (pin "1") (pinfunction "S_1") (pintype "passive"))
      (node (ref "S7") (pin "2") (pinfunction "S1_2") (pintype "passive"))
      (node (ref "U$2") (pin "2") (pinfunction "I7_2") (pintype "bidirectional"))
    )
    (net (code "43") (name "Net-(S8-S)") (class "Default")
      (node (ref "R47") (pin "2") (pinfunction "2_2") (pintype "passive"))
      (node (ref "S8") (pin "1") (pinfunction "S_1") (pintype "passive"))
      (node (ref "S8") (pin "2") (pinfunction "S1_2") (pintype "passive"))
      (node (ref "U$2") (pin "3") (pinfunction "I6_3") (pintype "bidirectional"))
    )
    (net (code "44") (name "Net-(S9-S)") (class "Default")
      (node (ref "R46") (pin "2") (pinfunction "2_2") (pintype "passive"))
      (node (ref "S9") (pin "1") (pinfunction "S_1") (pintype "passive"))
      (node (ref "S9") (pin "2") (pinfunction "S1_2") (pintype "passive"))
      (node (ref "U$2") (pin "4") (pinfunction "I5_4") (pintype "bidirectional"))
    )
    (net (code "45") (name "Net-(S10-S)") (class "Default")
      (node (ref "R45") (pin "2") (pinfunction "2_2") (pintype "passive"))
      (node (ref "S10") (pin "1") (pinfunction "S_1") (pintype "passive"))
      (node (ref "S10") (pin "2") (pinfunction "S1_2") (pintype "passive"))
      (node (ref "U$2") (pin "5") (pinfunction "I4_5") (pintype "bidirectional"))
    )
    (net (code "46") (name "Net-(S11-S)") (class "Default")
      (node (ref "R44") (pin "2") (pinfunction "2_2") (pintype "passive"))
      (node (ref "S11") (pin "1") (pinfunction "S_1") (pintype "passive"))
      (node (ref "S11") (pin "2") (pinfunction "S1_2") (pintype "passive"))
      (node (ref "U$2") (pin "6") (pinfunction "I3_6") (pintype "bidirectional"))
    )
    (net (code "47") (name "Net-(S12-S)") (class "Default")
      (node (ref "R43") (pin "2") (pinfunction "2_2") (pintype "passive"))
      (node (ref "S12") (pin "1") (pinfunction "S_1") (pintype "passive"))
      (node (ref "S12") (pin "2") (pinfunction "S1_2") (pintype "passive"))
      (node (ref "U$2") (pin "7") (pinfunction "I2_7") (pintype "bidirectional"))
    )
    (net (code "48") (name "Net-(S13-S)") (class "Default")
      (node (ref "R42") (pin "2") (pinfunction "2_2") (pintype "passive"))
      (node (ref "S13") (pin "1") (pinfunction "S_1") (pintype "passive"))
      (node (ref "S13") (pin "2") (pinfunction "S1_2") (pintype "passive"))
      (node (ref "U$2") (pin "8") (pinfunction "I1_8") (pintype "bidirectional"))
    )
    (net (code "49") (name "Net-(S14-S)") (class "Default")
      (node (ref "R41") (pin "2") (pinfunction "2_2") (pintype "passive"))
      (node (ref "S14") (pin "1") (pinfunction "S_1") (pintype "passive"))
      (node (ref "S14") (pin "2") (pinfunction "S1_2") (pintype "passive"))
      (node (ref "U$2") (pin "9") (pinfunction "I0_9") (pintype "bidirectional"))
    )
    (net (code "50") (name "Net-(SR1A-G)") (class "Default")
      (node (ref "SR1") (pin "13") (pinfunction "G_13") (pintype "input"))
      (node (ref "SR2") (pin "13") (pinfunction "G_13") (pintype "input"))
      (node (ref "U$1") (pin "13") (pinfunction "(AIN1)PB1_13") (pintype "bidirectional"))
    )
    (net (code "51") (name "Net-(SR1A-QA)") (class "Default")
      (node (ref "R9") (pin "1") (pinfunction "1_1") (pintype "passive"))
      (node (ref "SR1") (pin "15") (pinfunction "QA_15") (pintype "tri_state"))
    )
    (net (code "52") (name "Net-(SR1A-QB)") (class "Default")
      (node (ref "R10") (pin "1") (pinfunction "1_1") (pintype "passive"))
      (node (ref "SR1") (pin "1") (pinfunction "QB_1") (pintype "tri_state"))
    )
    (net (code "53") (name "Net-(SR1A-QC)") (class "Default")
      (node (ref "R11") (pin "1") (pinfunction "1_1") (pintype "passive"))
      (node (ref "SR1") (pin "2") (pinfunction "QC_2") (pintype "tri_state"))
    )
    (net (code "54") (name "Net-(SR1A-QD)") (class "Default")
      (node (ref "R12") (pin "1") (pinfunction "1_1") (pintype "passive"))
      (node (ref "SR1") (pin "3") (pinfunction "QD_3") (pintype "tri_state"))
    )
    (net (code "55") (name "Net-(SR1A-QE)") (class "Default")
      (node (ref "R13") (pin "1") (pinfunction "1_1") (pintype "passive"))
      (node (ref "SR1") (pin "4") (pinfunction "QE_4") (pintype "tri_state"))
    )
    (net (code "56") (name "Net-(SR1A-QF)") (class "Default")
      (node (ref "R14") (pin "1") (pinfunction "1_1") (pintype "passive"))
      (node (ref "SR1") (pin "5") (pinfunction "QF_5") (pintype "tri_state"))
    )
    (net (code "57") (name "Net-(SR1A-QG)") (class "Default")
      (node (ref "R15") (pin "1") (pinfunction "1_1") (pintype "passive"))
      (node (ref "SR1") (pin "6") (pinfunction "QG_6") (pintype "tri_state"))
    )
    (net (code "58") (name "Net-(SR1A-QH)") (class "Default")
      (node (ref "R16") (pin "1") (pinfunction "1_1") (pintype "passive"))
      (node (ref "SR1") (pin "7") (pinfunction "QH_7") (pintype "tri_state"))
    )
    (net (code "59") (name "Net-(SR1A-QH*)") (class "Default")
      (node (ref "SR1") (pin "9") (pinfunction "QH*_9") (pintype "tri_state"))
      (node (ref "SR2") (pin "14") (pinfunction "SER_14") (pintype "input"))
    )
    (net (code "60") (name "Net-(SR1A-RCK)") (class "Default")
      (node (ref "SR1") (pin "12") (pinfunction "RCK_12") (pintype "input"))
      (node (ref "SR2") (pin "12") (pinfunction "RCK_12") (pintype "input"))
      (node (ref "U$1") (pin "14") (pinfunction "(OC0A)PB2_14") (pintype "bidirectional"))
    )
    (net (code "61") (name "Net-(SR1A-SCK)") (class "Default")
      (node (ref "SR1") (pin "11") (pinfunction "SCK_11") (pintype "input"))
      (node (ref "SR2") (pin "11") (pinfunction "SCK_11") (pintype "input"))
      (node (ref "U$1") (pin "15") (pinfunction "(OC1A)PB3_15") (pintype "bidirectional"))
    )
    (net (code "62") (name "Net-(SR1A-SCL)") (class "Default")
      (node (ref "SR1") (pin "10") (pinfunction "SCL_10") (pintype "input"))
      (node (ref "SR2") (pin "10") (pinfunction "SCL_10") (pintype "input"))
      (node (ref "U$1") (pin "16") (pinfunction "(OC1B)PB4_16") (pintype "bidirectional"))
    )
    (net (code "63") (name "Net-(SR1A-SER)") (class "Default")
      (node (ref "SR1") (pin "14") (pinfunction "SER_14") (pintype "input"))
      (node (ref "U$1") (pin "12") (pinfunction "(AIN0)PB0_12") (pintype "bidirectional"))
    )
    (net (code "64") (name "Net-(SR2A-QA)") (class "Default")
      (node (ref "R24") (pin "1") (pinfunction "1_1") (pintype "passive"))
      (node (ref "SR2") (pin "15") (pinfunction "QA_15") (pintype "tri_state"))
    )
    (net (code "65") (name "Net-(SR2A-QB)") (class "Default")
      (node (ref "R23") (pin "1") (pinfunction "1_1") (pintype "passive"))
      (node (ref "SR2") (pin "1") (pinfunction "QB_1") (pintype "tri_state"))
    )
    (net (code "66") (name "Net-(SR2A-QC)") (class "Default")
      (node (ref "R22") (pin "1") (pinfunction "1_1") (pintype "passive"))
      (node (ref "SR2") (pin "2") (pinfunction "QC_2") (pintype "tri_state"))
    )
    (net (code "67") (name "Net-(SR2A-QD)") (class "Default")
      (node (ref "R21") (pin "1") (pinfunction "1_1") (pintype "passive"))
      (node (ref "SR2") (pin "3") (pinfunction "QD_3") (pintype "tri_state"))
    )
    (net (code "68") (name "Net-(SR2A-QE)") (class "Default")
      (node (ref "R20") (pin "1") (pinfunction "1_1") (pintype "passive"))
      (node (ref "SR2") (pin "4") (pinfunction "QE_4") (pintype "tri_state"))
    )
    (net (code "69") (name "Net-(SR2A-QF)") (class "Default")
      (node (ref "R19") (pin "1") (pinfunction "1_1") (pintype "passive"))
      (node (ref "SR2") (pin "5") (pinfunction "QF_5") (pintype "tri_state"))
    )
    (net (code "70") (name "Net-(SR2A-QG)") (class "Default")
      (node (ref "R18") (pin "1") (pinfunction "1_1") (pintype "passive"))
      (node (ref "SR2") (pin "6") (pinfunction "QG_6") (pintype "tri_state"))
    )
    (net (code "71") (name "Net-(SR2A-QH)") (class "Default")
      (node (ref "R17") (pin "1") (pinfunction "1_1") (pintype "passive"))
      (node (ref "SR2") (pin "7") (pinfunction "QH_7") (pintype "tri_state"))
    )
    (net (code "72") (name "Net-(T1-B)") (class "Default")
      (node (ref "R9") (pin "2") (pinfunction "2_2") (pintype "passive"))
      (node (ref "T1") (pin "2") (pinfunction "B_2") (pintype "passive"))
    )
    (net (code "73") (name "Net-(T2-B)") (class "Default")
      (node (ref "R10") (pin "2") (pinfunction "2_2") (pintype "passive"))
      (node (ref "T2") (pin "2") (pinfunction "B_2") (pintype "passive"))
    )
    (net (code "74") (name "Net-(T3-B)") (class "Default")
      (node (ref "R11") (pin "2") (pinfunction "2_2") (pintype "passive"))
      (node (ref "T3") (pin "2") (pinfunction "B_2") (pintype "passive"))
    )
    (net (code "75") (name "Net-(T4-B)") (class "Default")
      (node (ref "R12") (pin "2") (pinfunction "2_2") (pintype "passive"))
      (node (ref "T4") (pin "2") (pinfunction "B_2") (pintype "passive"))
    )
    (net (code "76") (name "Net-(T5-B)") (class "Default")
      (node (ref "R13") (pin "2") (pinfunction "2_2") (pintype "passive"))
      (node (ref "T5") (pin "2") (pinfunction "B_2") (pintype "passive"))
    )
    (net (code "77") (name "Net-(T6-B)") (class "Default")
      (node (ref "R14") (pin "2") (pinfunction "2_2") (pintype "passive"))
      (node (ref "T6") (pin "2") (pinfunction "B_2") (pintype "passive"))
    )
    (net (code "78") (name "Net-(T7-B)") (class "Default")
      (node (ref "R15") (pin "2") (pinfunction "2_2") (pintype "passive"))
      (node (ref "T7") (pin "2") (pinfunction "B_2") (pintype "passive"))
    )
    (net (code "79") (name "Net-(T8-B)") (class "Default")
      (node (ref "R16") (pin "2") (pinfunction "2_2") (pintype "passive"))
      (node (ref "T8") (pin "2") (pinfunction "B_2") (pintype "passive"))
    )
    (net (code "80") (name "Net-(T9-B)") (class "Default")
      (node (ref "R17") (pin "2") (pinfunction "2_2") (pintype "passive"))
      (node (ref "T9") (pin "2") (pinfunction "B_2") (pintype "passive"))
    )
    (net (code "81") (name "Net-(T10-B)") (class "Default")
      (node (ref "R18") (pin "2") (pinfunction "2_2") (pintype "passive"))
      (node (ref "T10") (pin "2") (pinfunction "B_2") (pintype "passive"))
    )
    (net (code "82") (name "Net-(T11-B)") (class "Default")
      (node (ref "R19") (pin "2") (pinfunction "2_2") (pintype "passive"))
      (node (ref "T11") (pin "2") (pinfunction "B_2") (pintype "passive"))
    )
    (net (code "83") (name "Net-(T12-B)") (class "Default")
      (node (ref "R20") (pin "2") (pinfunction "2_2") (pintype "passive"))
      (node (ref "T12") (pin "2") (pinfunction "B_2") (pintype "passive"))
    )
    (net (code "84") (name "Net-(T13-B)") (class "Default")
      (node (ref "R21") (pin "2") (pinfunction "2_2") (pintype "passive"))
      (node (ref "T13") (pin "2") (pinfunction "B_2") (pintype "passive"))
    )
    (net (code "85") (name "Net-(T14-B)") (class "Default")
      (node (ref "R22") (pin "2") (pinfunction "2_2") (pintype "passive"))
      (node (ref "T14") (pin "2") (pinfunction "B_2") (pintype "passive"))
    )
    (net (code "86") (name "Net-(T15-B)") (class "Default")
      (node (ref "R23") (pin "2") (pinfunction "2_2") (pintype "passive"))
      (node (ref "T15") (pin "2") (pinfunction "B_2") (pintype "passive"))
    )
    (net (code "87") (name "Net-(T16-B)") (class "Default")
      (node (ref "R24") (pin "2") (pinfunction "2_2") (pintype "passive"))
      (node (ref "T16") (pin "2") (pinfunction "B_2") (pintype "passive"))
    )
    (net (code "88") (name "Net-(U$1-(INT0)PD2)") (class "Default")
      (node (ref "U$1") (pin "6") (pinfunction "(INT0)PD2_6") (pintype "bidirectional"))
      (node (ref "U$2") (pin "11") (pinfunction "S1_11") (pintype "bidirectional"))
    )
    (net (code "89") (name "Net-(U$1-(INT1)PD3)") (class "Default")
      (node (ref "U$1") (pin "7") (pinfunction "(INT1)PD3_7") (pintype "bidirectional"))
      (node (ref "U$2") (pin "13") (pinfunction "S3_13") (pintype "bidirectional"))
    )
    (net (code "90") (name "Net-(U$1-(RXD)PD0)") (class "Default")
      (node (ref "U$1") (pin "2") (pinfunction "(RXD)PD0_2") (pintype "bidirectional"))
      (node (ref "U$2") (pin "1") (pinfunction "COM_I/O_1") (pintype "bidirectional"))
    )
    (net (code "91") (name "Net-(U$1-(T0)PD4)") (class "Default")
      (node (ref "U$1") (pin "8") (pinfunction "(T0)PD4_8") (pintype "bidirectional"))
      (node (ref "U$2") (pin "14") (pinfunction "S2_14") (pintype "bidirectional"))
    )
    (net (code "92") (name "Net-(U$1-(TXD)PD1)") (class "Default")
      (node (ref "U$1") (pin "3") (pinfunction "(TXD)PD1_3") (pintype "bidirectional"))
      (node (ref "U$2") (pin "10") (pinfunction "S0_10") (pintype "bidirectional"))
    )
    (net (code "93") (name "Net-(U$1-PA2({slash}RESET))") (class "Default")
      (node (ref "R33") (pin "2") (pinfunction "2_2") (pintype "passive"))
      (node (ref "U$1") (pin "1") (pinfunction "PA2(/RESET)_1") (pintype "input"))
    )
    (net (code "94") (name "unconnected-(SR2A-QH*-Pad9)") (class "Default")
      (node (ref "SR2") (pin "9") (pinfunction "QH*_9") (pintype "tri_state"))
    )
    (net (code "95") (name "unconnected-(U$1-(ICP)PD6-Pad11)") (class "Default")
      (node (ref "U$1") (pin "11") (pinfunction "(ICP)PD6_11") (pintype "bidirectional"))
    )
    (net (code "96") (name "unconnected-(U$1-(MISO)PB6-Pad18)") (class "Default")
      (node (ref "U$1") (pin "18") (pinfunction "(MISO)PB6_18") (pintype "bidirectional"))
    )
    (net (code "97") (name "unconnected-(U$1-(MOSI)PB5-Pad17)") (class "Default")
      (node (ref "U$1") (pin "17") (pinfunction "(MOSI)PB5_17") (pintype "bidirectional"))
    )
    (net (code "98") (name "unconnected-(U$1-(T1)PD5-Pad9)") (class "Default")
      (node (ref "U$1") (pin "9") (pinfunction "(T1)PD5_9") (pintype "bidirectional"))
    )
    (net (code "99") (name "unconnected-(U$1-(UCSK)PB7-Pad19)") (class "Default")
      (node (ref "U$1") (pin "19") (pinfunction "(UCSK)PB7_19") (pintype "bidirectional"))
    )
    (net (code "100") (name "unconnected-(U$1-PA0(XTAL1)-Pad5)") (class "Default")
      (node (ref "U$1") (pin "5") (pinfunction "PA0(XTAL1)_5") (pintype "bidirectional"))
    )
    (net (code "101") (name "unconnected-(U$1-PA1(XTAL2)-Pad4)") (class "Default")
      (node (ref "U$1") (pin "4") (pinfunction "PA1(XTAL2)_4") (pintype "bidirectional"))
    )
    (net (code "102") (name "unconnected-(U$2-I14-Pad17)") (class "Default")
      (node (ref "U$2") (pin "17") (pinfunction "I14_17") (pintype "bidirectional"))
    )
    (net (code "103") (name "unconnected-(U$2-I15-Pad16)") (class "Default")
      (node (ref "U$2") (pin "16") (pinfunction "I15_16") (pintype "bidirectional"))
    )
  )
)
